# mag_encoder.net
KiCad netlist of a schematic drawn in Altium Designer
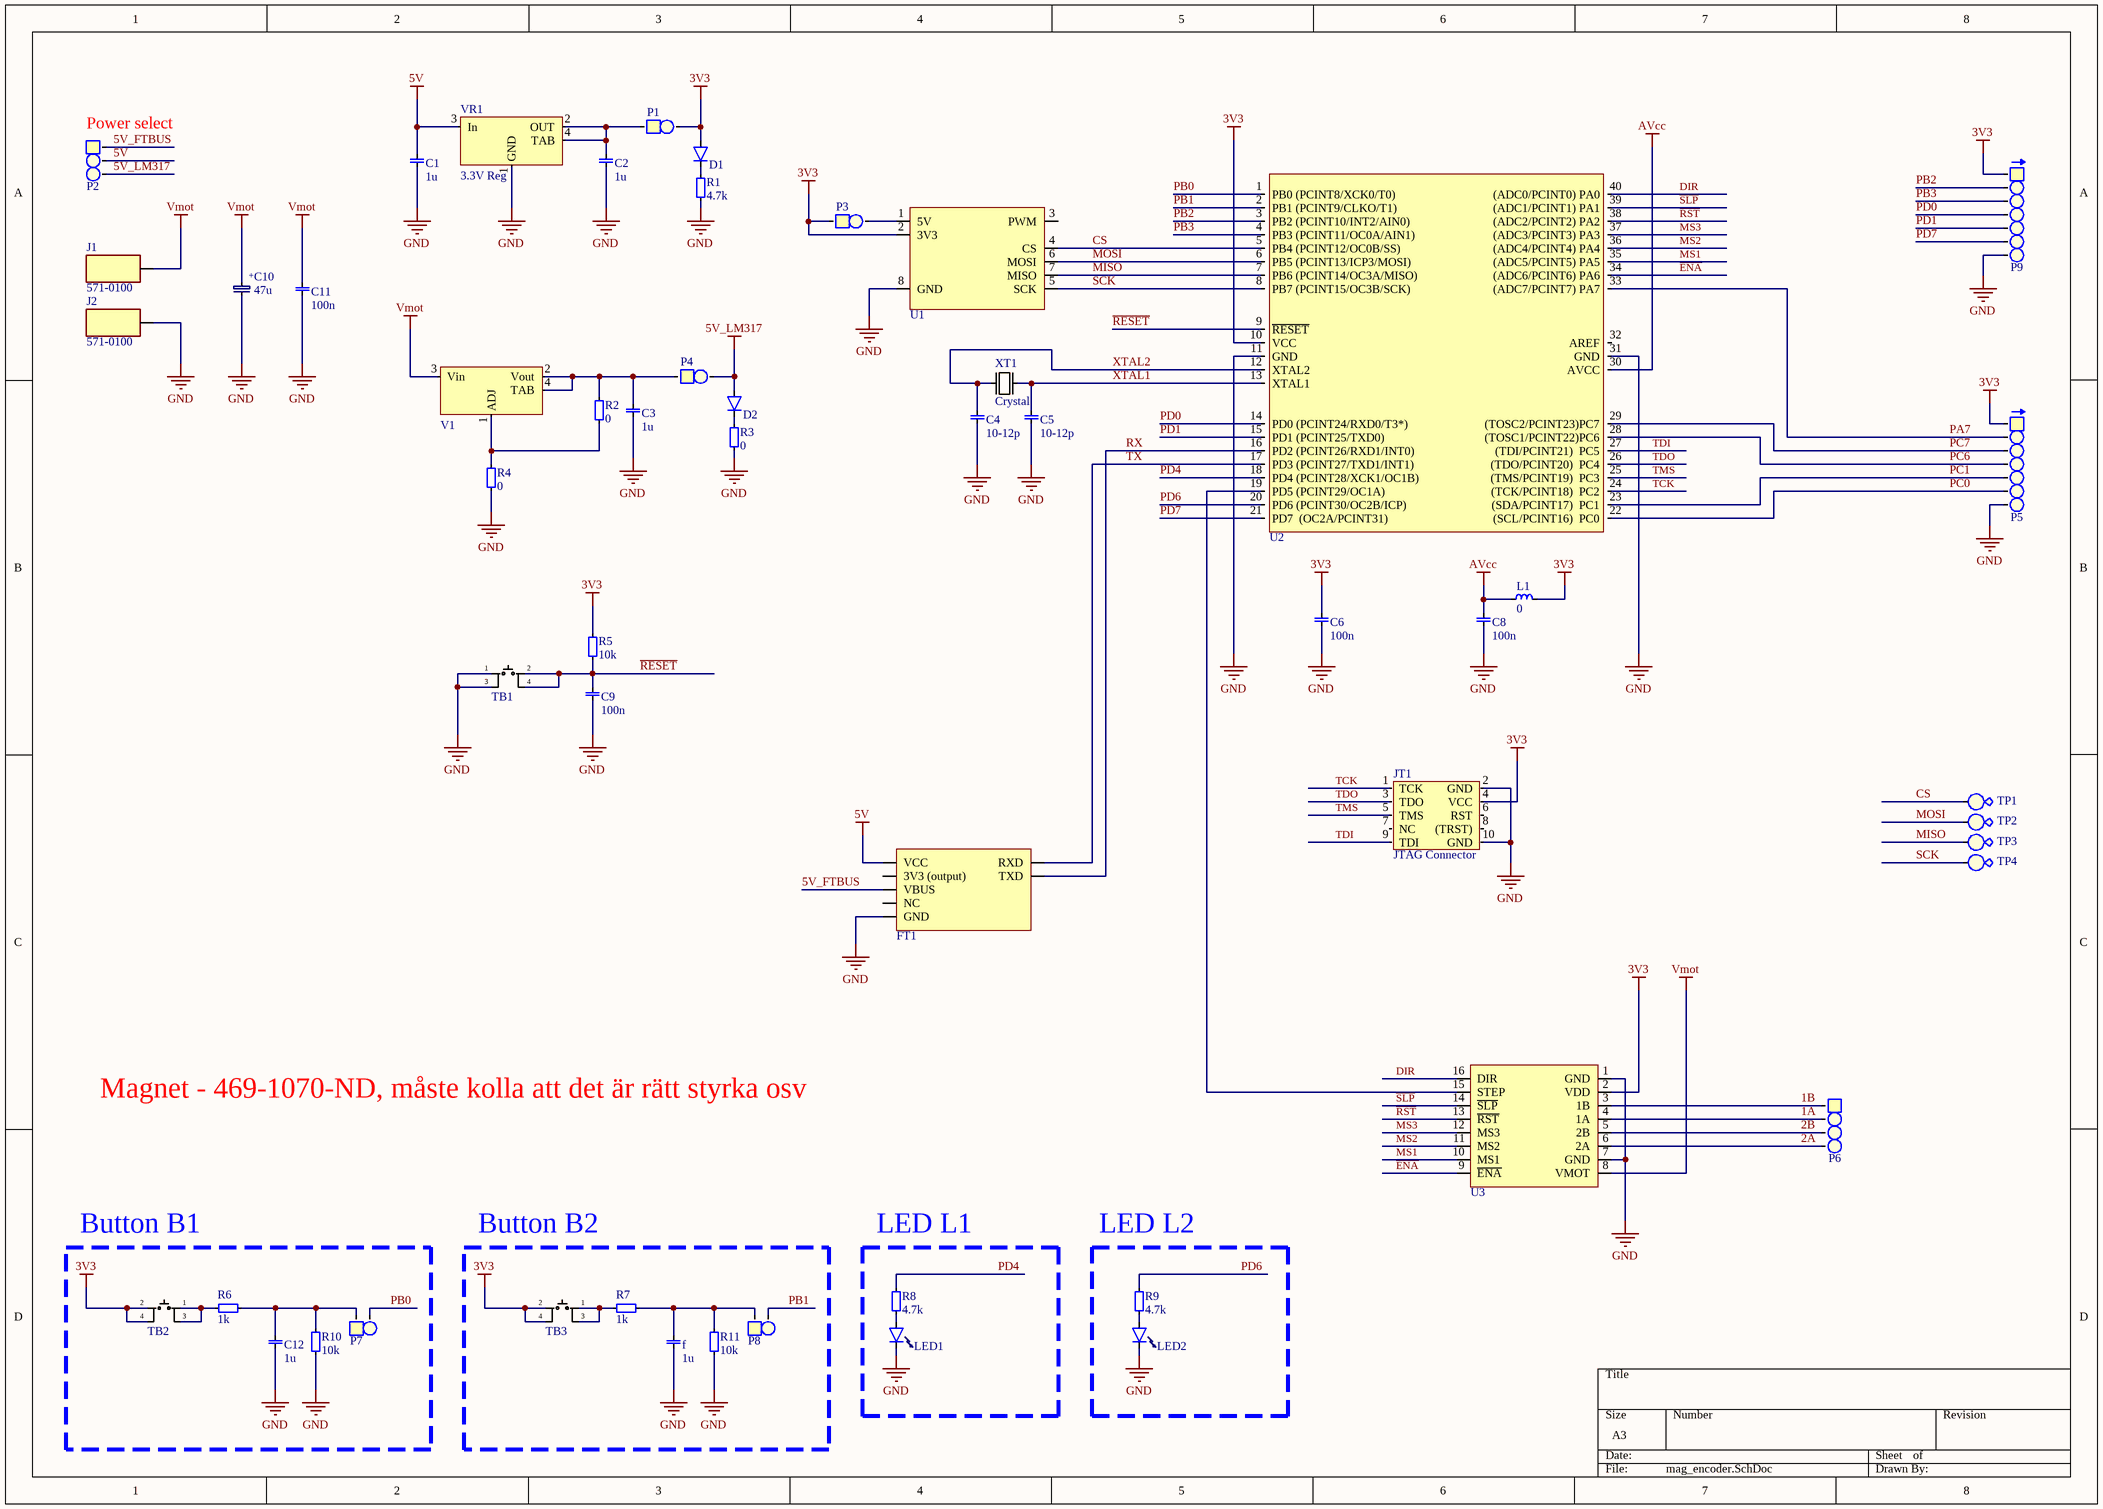
[diagram p0: mag_encoder.SchDoc]

(export (version "E")
  (design (tool "Eeschema 10.0.6"))
  (components
    (comp (ref "C1")
      (value "1u")
      (footprint "0603 cap")
      (fields (field (name "Comment") "0603, capacitor"))
      (libsource (lib "jclib") (part "0603, capacitor"))
    )
    (comp (ref "C2")
      (value "1u")
      (footprint "0603 cap")
      (fields (field (name "Comment") "0603, capacitor"))
      (libsource (lib "jclib") (part "0603, capacitor"))
    )
    (comp (ref "C3")
      (value "1u")
      (footprint "0603 cap")
      (fields (field (name "Comment") "0603, capacitor"))
      (libsource (lib "jclib") (part "0603, capacitor"))
    )
    (comp (ref "C4")
      (value "10-12p")
      (footprint "0603 cap")
      (fields (field (name "Comment") "0603, capacitor"))
      (libsource (lib "jclib") (part "0603, capacitor"))
    )
    (comp (ref "C5")
      (value "10-12p")
      (footprint "0603 cap")
      (fields (field (name "Comment") "0603, capacitor"))
      (libsource (lib "jclib") (part "0603, capacitor"))
    )
    (comp (ref "C6")
      (value "100n")
      (footprint "0603 cap")
      (fields (field (name "Comment") "0603, capacitor"))
      (libsource (lib "jclib") (part "0603, capacitor"))
    )
    (comp (ref "C8")
      (value "100n")
      (footprint "0603 cap")
      (fields (field (name "Comment") "0603, capacitor"))
      (libsource (lib "jclib") (part "0603, capacitor"))
    )
    (comp (ref "C9")
      (value "100n")
      (footprint "0603 cap")
      (fields (field (name "Comment") "0603, capacitor"))
      (libsource (lib "jclib") (part "0603, capacitor"))
    )
    (comp (ref "C10")
      (value "47u")
      (footprint "CASE_B")
      (fields (field (name "Comment") "Cap, case B"))
      (libsource (lib "jclib") (part "Cap, case B"))
    )
    (comp (ref "C11")
      (value "100n")
      (footprint "0805, cap")
      (fields (field (name "Comment") "0805, capacitor"))
      (libsource (lib "jclib") (part "0805, capacitor"))
    )
    (comp (ref "C12")
      (value "1u")
      (footprint "0603 cap")
      (fields (field (name "Comment") "0603, capacitor"))
      (libsource (lib "jclib") (part "0603, capacitor"))
    )
    (comp (ref "D1")
      (value "0805, diode")
      (footprint "0805 diode")
      (libsource (lib "jclib") (part "0805, diode"))
    )
    (comp (ref "D2")
      (value "0805, diode")
      (footprint "0805 diode")
      (libsource (lib "jclib") (part "0805, diode"))
    )
    (comp (ref "f")
      (value "1u")
      (footprint "0603 cap")
      (fields (field (name "Comment") "0603, capacitor"))
      (libsource (lib "jclib") (part "0603, capacitor"))
    )
    (comp (ref "FT1")
      (value "FT232_pcb")
      (footprint "ft2323_pcb")
      (libsource (lib "jclib") (part "FT232_pcb"))
    )
    (comp (ref "J1")
      (value "571-0100")
      (footprint "Banana Conn VCC")
      (description "Banana Connector 571-0100")
      (fields (field (name "MOUSER PART NUMBER") "164-6218"))
      (libsource (lib "jclib") (part "Banana conn"))
    )
    (comp (ref "J2")
      (value "571-0100")
      (footprint "Banana Conn GND")
      (description "Banana Connector 571-0100")
      (fields (field (name "MOUSER PART NUMBER") "164-6218"))
      (libsource (lib "jclib") (part "Banana conn"))
    )
    (comp (ref "JT1")
      (value "JTAG Connector")
      (footprint "Atmel_JTAG")
      (description "Atmel JTAG Connector")
      (libsource (lib "jclib") (part "Atmel JTAG"))
    )
    (comp (ref "L1")
      (value "0")
      (footprint "1812, coil")
      (fields (field (name "Comment") "Coil"))
      (libsource (lib "jclib") (part "Coil"))
    )
    (comp (ref "LED1")
      (value "0805, LED")
      (footprint "0805_led")
      (libsource (lib "eitp15_lab1_lib") (part "0805, LED"))
    )
    (comp (ref "LED2")
      (value "0805, LED")
      (footprint "0805_led")
      (libsource (lib "eitp15_lab1_lib") (part "0805, LED"))
    )
    (comp (ref "P1")
      (value "1x2 Pin Header Straight")
      (footprint "padtwo_L")
      (description "2.54 mm, TH")
      (libsource (lib "jclib") (part "1x2 Pin Header Straight"))
    )
    (comp (ref "P2")
      (value "1x3 Pin Header")
      (footprint "padThree_L")
      (description "2.54 mm")
      (libsource (lib "jclib") (part "1x3 Pin Header"))
    )
    (comp (ref "P3")
      (value "1x2 Pin Header Straight")
      (footprint "padtwo_L")
      (description "2.54 mm, TH")
      (libsource (lib "jclib") (part "1x2 Pin Header Straight"))
    )
    (comp (ref "P4")
      (value "1x2 Pin Header Straight")
      (footprint "padtwo_L")
      (description "2.54 mm, TH")
      (libsource (lib "jclib") (part "1x2 Pin Header Straight"))
    )
    (comp (ref "P5")
      (value "1x7 Pin Header")
      (footprint "1x7 Pin Header")
      (description "2.54 mm")
      (libsource (lib "jclib") (part "1x7 Pin Header"))
    )
    (comp (ref "P6")
      (value "4x1 Pin Header")
      (footprint "padFour_L")
      (description "2.54 mm")
      (libsource (lib "jclib") (part "1x4 Pin Header"))
    )
    (comp (ref "P7")
      (value "1x2 Pin Header")
      (footprint "1x2HEADER")
      (description "2.54 mm, TH")
      (libsource (lib "eitp15_lab1_lib") (part "1x2 Pin Header"))
    )
    (comp (ref "P8")
      (value "1x2 Pin Header")
      (footprint "1x2HEADER")
      (description "2.54 mm, TH")
      (libsource (lib "eitp15_lab1_lib") (part "1x2 Pin Header"))
    )
    (comp (ref "P9")
      (value "1x7 Pin Header")
      (footprint "1x7 Pin Header")
      (description "2.54 mm")
      (libsource (lib "jclib") (part "1x7 Pin Header"))
    )
    (comp (ref "R1")
      (value "4.7k")
      (footprint "0603")
      (fields (field (name "Comment") "0603, resistor"))
      (libsource (lib "jclib") (part "0603, resistor"))
    )
    (comp (ref "R2")
      (value "0")
      (footprint "0603")
      (fields (field (name "Comment") "0603, resistor"))
      (libsource (lib "jclib") (part "0603, resistor"))
    )
    (comp (ref "R3")
      (value "0")
      (footprint "0603")
      (fields (field (name "Comment") "0603, resistor"))
      (libsource (lib "jclib") (part "0603, resistor"))
    )
    (comp (ref "R4")
      (value "0")
      (footprint "0603")
      (fields (field (name "Comment") "0603, resistor"))
      (libsource (lib "jclib") (part "0603, resistor"))
    )
    (comp (ref "R5")
      (value "10k")
      (footprint "0603")
      (fields (field (name "Comment") "0603, resistor"))
      (libsource (lib "jclib") (part "0603, resistor"))
    )
    (comp (ref "R6")
      (value "1k")
      (footprint "0603")
      (fields (field (name "Comment") "0603, resistor"))
      (libsource (lib "jclib") (part "0603, resistor"))
    )
    (comp (ref "R7")
      (value "1k")
      (footprint "0603")
      (fields (field (name "Comment") "0603, resistor"))
      (libsource (lib "jclib") (part "0603, resistor"))
    )
    (comp (ref "R8")
      (value "4.7k")
      (footprint "0603")
      (fields (field (name "Comment") "0603, resistor"))
      (libsource (lib "jclib") (part "0603, resistor"))
    )
    (comp (ref "R9")
      (value "4.7k")
      (footprint "0603")
      (fields (field (name "Comment") "0603, resistor"))
      (libsource (lib "jclib") (part "0603, resistor"))
    )
    (comp (ref "R10")
      (value "10k")
      (footprint "0603")
      (fields (field (name "Comment") "0603, resistor"))
      (libsource (lib "jclib") (part "0603, resistor"))
    )
    (comp (ref "R11")
      (value "10k")
      (footprint "0603")
      (fields (field (name "Comment") "0603, resistor"))
      (libsource (lib "jclib") (part "0603, resistor"))
    )
    (comp (ref "TB1")
      (value "Tactile Button")
      (footprint "Button smd")
      (description "Tactile Switch Small Low")
      (libsource (lib "eitp15_lab1_lib") (part "Button SMD"))
    )
    (comp (ref "TB2")
      (value "Tactile Button")
      (footprint "Button smd")
      (description "Tactile Switch Small Low")
      (libsource (lib "eitp15_lab1_lib") (part "Button SMD"))
    )
    (comp (ref "TB3")
      (value "Tactile Button")
      (footprint "Button smd")
      (description "Tactile Switch Small Low")
      (libsource (lib "eitp15_lab1_lib") (part "Button SMD"))
    )
    (comp (ref "TP1")
      (value "Test Point")
      (footprint "testPoint")
      (libsource (lib "jclib") (part "Test Point"))
    )
    (comp (ref "TP2")
      (value "Test Point")
      (footprint "testPoint")
      (libsource (lib "jclib") (part "Test Point"))
    )
    (comp (ref "TP3")
      (value "Test Point")
      (footprint "testPoint")
      (libsource (lib "jclib") (part "Test Point"))
    )
    (comp (ref "TP4")
      (value "Test Point")
      (footprint "testPoint")
      (libsource (lib "jclib") (part "Test Point"))
    )
    (comp (ref "U1")
      (value "as5048_module")
      (footprint "AS5048_MODULE")
      (description "AS5048 Rotary encoder")
      (libsource (lib "jclib") (part "as5048_module"))
    )
    (comp (ref "U2")
      (value "ATmega1284")
      (footprint "DIP40")
      (description "8-bit Atmel Microcontroller with 128K Bytes  In-System Programmable Flash")
      (libsource (lib "jclib") (part "ATmega1284"))
    )
    (comp (ref "U3")
      (value "A4988_stepstick")
      (footprint "A4988_stepstick")
      (libsource (lib "jclib") (part "A4988_stepstick"))
    )
    (comp (ref "V1")
      (value "LM317")
      (footprint "SOT223")
      (description "Adjustable Voltage Regulator")
      (libsource (lib "jclib") (part "LM317 SOT223"))
    )
    (comp (ref "VR1")
      (value "3.3V Reg")
      (footprint "SOT223")
      (description "TLV1117LV 1-A, Positive Fixed-Voltage, Low-Dropout Regulator")
      (libsource (lib "jclib") (part "TLV1117LV"))
    )
    (comp (ref "XT1")
      (value "Crystal")
      (footprint "XTAL_SMD_LP")
      (description "16 MHz, SMD, 5mm x 3,2mm, 30 ppm")
      (fields (field (name "Comment") "XTAL TXC 7A"))
      (libsource (lib "eitp15_lab1_lib") (part "XTAL TXC 7A"))
    )
  )
  (nets
    (net (code "1") (name "/1A") (class "Default")
      (node (ref "P6") (pin "2") (pinfunction "2_2") (pintype "passive"))
      (node (ref "U3") (pin "4") (pinfunction "1A_4") (pintype "passive"))
    )
    (net (code "2") (name "/1B") (class "Default")
      (node (ref "P6") (pin "1") (pinfunction "1_1") (pintype "passive"))
      (node (ref "U3") (pin "3") (pinfunction "1B_3") (pintype "passive"))
    )
    (net (code "3") (name "/2A") (class "Default")
      (node (ref "P6") (pin "4") (pinfunction "4_4") (pintype "passive"))
      (node (ref "U3") (pin "6") (pinfunction "2A_6") (pintype "passive"))
    )
    (net (code "4") (name "/2B") (class "Default")
      (node (ref "P6") (pin "3") (pinfunction "3_3") (pintype "passive"))
      (node (ref "U3") (pin "5") (pinfunction "2B_5") (pintype "passive"))
    )
    (net (code "5") (name "/5V_FTBUS") (class "Default")
      (node (ref "FT1") (pin "3") (pinfunction "VBUS_3") (pintype "passive"))
      (node (ref "P2") (pin "1") (pinfunction "1_1") (pintype "passive"))
    )
    (net (code "6") (name "/CS") (class "Default")
      (node (ref "TP1") (pin "0") (pinfunction "0_0") (pintype "passive"))
      (node (ref "U1") (pin "4") (pinfunction "CS_4") (pintype "passive"))
      (node (ref "U2") (pin "5") (pinfunction "PB4_(PCINT12/OC0B/SS)_5") (pintype "passive"))
    )
    (net (code "7") (name "/DIR") (class "Default")
      (node (ref "U2") (pin "40") (pinfunction "(ADC0/PCINT0)_PA0_40") (pintype "passive"))
      (node (ref "U3") (pin "16") (pinfunction "DIR_16") (pintype "passive"))
    )
    (net (code "8") (name "/MISO") (class "Default")
      (node (ref "TP3") (pin "0") (pinfunction "0_0") (pintype "passive"))
      (node (ref "U1") (pin "7") (pinfunction "MISO_7") (pintype "passive"))
      (node (ref "U2") (pin "7") (pinfunction "PB6_(PCINT14/OC3A/MISO)_7") (pintype "passive"))
    )
    (net (code "9") (name "/MOSI") (class "Default")
      (node (ref "TP2") (pin "0") (pinfunction "0_0") (pintype "passive"))
      (node (ref "U1") (pin "6") (pinfunction "MOSI_6") (pintype "passive"))
      (node (ref "U2") (pin "6") (pinfunction "PB5_(PCINT13/ICP3/MOSI)_6") (pintype "passive"))
    )
    (net (code "10") (name "/MS1") (class "Default")
      (node (ref "U2") (pin "35") (pinfunction "(ADC5/PCINT5)_PA5_35") (pintype "passive"))
      (node (ref "U3") (pin "10") (pinfunction "MS1_10") (pintype "passive"))
    )
    (net (code "11") (name "/MS2") (class "Default")
      (node (ref "U2") (pin "36") (pinfunction "(ADC4/PCINT4)_PA4_36") (pintype "passive"))
      (node (ref "U3") (pin "11") (pinfunction "MS2_11") (pintype "passive"))
    )
    (net (code "12") (name "/MS3") (class "Default")
      (node (ref "U2") (pin "37") (pinfunction "(ADC3/PCINT3)_PA3_37") (pintype "passive"))
      (node (ref "U3") (pin "12") (pinfunction "MS3_12") (pintype "passive"))
    )
    (net (code "13") (name "/PA7") (class "Default")
      (node (ref "P5") (pin "2") (pinfunction "2_2") (pintype "passive"))
      (node (ref "U2") (pin "33") (pinfunction "(ADC7/PCINT7)_PA7_33") (pintype "passive"))
    )
    (net (code "14") (name "/PB0") (class "Default")
      (node (ref "P7") (pin "2") (pinfunction "2_2") (pintype "passive"))
      (node (ref "U2") (pin "1") (pinfunction "PB0_(PCINT8/XCK0/T0)_1") (pintype "passive"))
    )
    (net (code "15") (name "/PB1") (class "Default")
      (node (ref "P8") (pin "2") (pinfunction "2_2") (pintype "passive"))
      (node (ref "U2") (pin "2") (pinfunction "PB1_(PCINT9/CLKO/T1)_2") (pintype "passive"))
    )
    (net (code "16") (name "/PB2") (class "Default")
      (node (ref "P9") (pin "2") (pinfunction "2_2") (pintype "passive"))
      (node (ref "U2") (pin "3") (pinfunction "PB2_(PCINT10/INT2/AIN0)_3") (pintype "passive"))
    )
    (net (code "17") (name "/PB3") (class "Default")
      (node (ref "P9") (pin "3") (pinfunction "3_3") (pintype "passive"))
      (node (ref "U2") (pin "4") (pinfunction "PB3_(PCINT11/OC0A/AIN1)_4") (pintype "passive"))
    )
    (net (code "18") (name "/PC0") (class "Default")
      (node (ref "P5") (pin "6") (pinfunction "6_6") (pintype "passive"))
      (node (ref "U2") (pin "22") (pinfunction "(SCL/PCINT16)__PC0_22") (pintype "passive"))
    )
    (net (code "19") (name "/PC1") (class "Default")
      (node (ref "P5") (pin "5") (pinfunction "5_5") (pintype "passive"))
      (node (ref "U2") (pin "23") (pinfunction "(SDA/PCINT17)__PC1_23") (pintype "passive"))
    )
    (net (code "20") (name "/PC6") (class "Default")
      (node (ref "P5") (pin "4") (pinfunction "4_4") (pintype "passive"))
      (node (ref "U2") (pin "28") (pinfunction "(TOSC1/PCINT22)PC6_28") (pintype "passive"))
    )
    (net (code "21") (name "/PC7") (class "Default")
      (node (ref "P5") (pin "3") (pinfunction "3_3") (pintype "passive"))
      (node (ref "U2") (pin "29") (pinfunction "(TOSC2/PCINT23)PC7_29") (pintype "passive"))
    )
    (net (code "22") (name "/PD0") (class "Default")
      (node (ref "P9") (pin "4") (pinfunction "4_4") (pintype "passive"))
      (node (ref "U2") (pin "14") (pinfunction "PD0_(PCINT24/RXD0/T3*)_14") (pintype "passive"))
    )
    (net (code "23") (name "/PD1") (class "Default")
      (node (ref "P9") (pin "5") (pinfunction "5_5") (pintype "passive"))
      (node (ref "U2") (pin "15") (pinfunction "PD1_(PCINT25/TXD0)_15") (pintype "passive"))
    )
    (net (code "24") (name "/PD4") (class "Default")
      (node (ref "R8") (pin "0") (pinfunction "0_0") (pintype "passive"))
      (node (ref "U2") (pin "18") (pinfunction "PD4_(PCINT28/XCK1/OC1B)_18") (pintype "passive"))
    )
    (net (code "25") (name "/PD6") (class "Default")
      (node (ref "R9") (pin "0") (pinfunction "0_0") (pintype "passive"))
      (node (ref "U2") (pin "20") (pinfunction "PD6_(PCINT30/OC2B/ICP)_20") (pintype "passive"))
    )
    (net (code "26") (name "/PD7") (class "Default")
      (node (ref "P9") (pin "6") (pinfunction "6_6") (pintype "passive"))
      (node (ref "U2") (pin "21") (pinfunction "PD7__(OC2A/PCINT31)_21") (pintype "passive"))
    )
    (net (code "27") (name "/RX") (class "Default")
      (node (ref "FT1") (pin "4") (pinfunction "TXD_4") (pintype "passive"))
      (node (ref "U2") (pin "16") (pinfunction "PD2_(PCINT26/RXD1/INT0)_16") (pintype "passive"))
    )
    (net (code "28") (name "/SCK") (class "Default")
      (node (ref "TP4") (pin "0") (pinfunction "0_0") (pintype "passive"))
      (node (ref "U1") (pin "5") (pinfunction "SCK_5") (pintype "passive"))
      (node (ref "U2") (pin "8") (pinfunction "PB7_(PCINT15/OC3B/SCK)_8") (pintype "passive"))
    )
    (net (code "29") (name "/TCK") (class "Default")
      (node (ref "JT1") (pin "1") (pinfunction "TCK_1") (pintype "passive"))
      (node (ref "U2") (pin "24") (pinfunction "(TCK/PCINT18)__PC2_24") (pintype "passive"))
    )
    (net (code "30") (name "/TDI") (class "Default")
      (node (ref "JT1") (pin "9") (pinfunction "TDI_9") (pintype "passive"))
      (node (ref "U2") (pin "27") (pinfunction "(TDI/PCINT21)__PC5_27") (pintype "passive"))
    )
    (net (code "31") (name "/TDO") (class "Default")
      (node (ref "JT1") (pin "3") (pinfunction "TDO_3") (pintype "passive"))
      (node (ref "U2") (pin "26") (pinfunction "(TDO/PCINT20)__PC4_26") (pintype "passive"))
    )
    (net (code "32") (name "/TMS") (class "Default")
      (node (ref "JT1") (pin "5") (pinfunction "TMS_5") (pintype "passive"))
      (node (ref "U2") (pin "25") (pinfunction "(TMS/PCINT19)__PC3_25") (pintype "passive"))
    )
    (net (code "33") (name "/TX") (class "Default")
      (node (ref "FT1") (pin "5") (pinfunction "RXD_5") (pintype "passive"))
      (node (ref "U2") (pin "17") (pinfunction "PD3_(PCINT27/TXD1/INT1)_17") (pintype "passive"))
    )
    (net (code "34") (name "/XTAL1") (class "Default")
      (node (ref "C5") (pin "1") (pinfunction "1_1") (pintype "passive"))
      (node (ref "U2") (pin "13") (pinfunction "XTAL1_13") (pintype "passive"))
      (node (ref "XT1") (pin "1") (pinfunction "1_1") (pintype "passive"))
    )
    (net (code "35") (name "/XTAL2") (class "Default")
      (node (ref "C4") (pin "1") (pinfunction "1_1") (pintype "passive"))
      (node (ref "U2") (pin "12") (pinfunction "XTAL2_12") (pintype "passive"))
      (node (ref "XT1") (pin "2") (pinfunction "2_2") (pintype "passive"))
    )
    (net (code "36") (name "/~{ENA}") (class "Default")
      (node (ref "U2") (pin "34") (pinfunction "(ADC6/PCINT6)_PA6_34") (pintype "passive"))
      (node (ref "U3") (pin "9") (pinfunction "~{ENA}_9") (pintype "passive"))
    )
    (net (code "37") (name "/~{RESET}") (class "Default")
      (node (ref "C9") (pin "1") (pinfunction "1_1") (pintype "passive"))
      (node (ref "R5") (pin "1") (pinfunction "1_1") (pintype "passive"))
      (node (ref "TB1") (pin "2") (pinfunction "2_2") (pintype "passive"))
      (node (ref "TB1") (pin "4") (pinfunction "4_4") (pintype "passive"))
      (node (ref "U2") (pin "9") (pinfunction "~{RESET}_9") (pintype "passive"))
    )
    (net (code "38") (name "/~{RST}") (class "Default")
      (node (ref "U2") (pin "38") (pinfunction "(ADC2/PCINT2)_PA2_38") (pintype "passive"))
      (node (ref "U3") (pin "13") (pinfunction "~{RST}_13") (pintype "passive"))
    )
    (net (code "39") (name "/~{SLP}") (class "Default")
      (node (ref "U2") (pin "39") (pinfunction "(ADC1/PCINT1)_PA1_39") (pintype "passive"))
      (node (ref "U3") (pin "14") (pinfunction "~{SLP}_14") (pintype "passive"))
    )
    (net (code "40") (name "3V3") (class "Default")
      (node (ref "C6") (pin "1") (pinfunction "1_1") (pintype "passive"))
      (node (ref "D1") (pin "1") (pinfunction "1_1") (pintype "passive"))
      (node (ref "JT1") (pin "4") (pinfunction "VCC_4") (pintype "passive"))
      (node (ref "L1") (pin "1") (pinfunction "1_1") (pintype "passive"))
      (node (ref "P1") (pin "2") (pinfunction "2_2") (pintype "passive"))
      (node (ref "P3") (pin "1") (pinfunction "1_1") (pintype "passive"))
      (node (ref "P5") (pin "1") (pinfunction "1_1") (pintype "passive"))
      (node (ref "P9") (pin "1") (pinfunction "1_1") (pintype "passive"))
      (node (ref "R5") (pin "0") (pinfunction "0_0") (pintype "passive"))
      (node (ref "TB2") (pin "2") (pinfunction "2_2") (pintype "passive"))
      (node (ref "TB2") (pin "4") (pinfunction "4_4") (pintype "passive"))
      (node (ref "TB3") (pin "2") (pinfunction "2_2") (pintype "passive"))
      (node (ref "TB3") (pin "4") (pinfunction "4_4") (pintype "passive"))
      (node (ref "U1") (pin "2") (pinfunction "3V3_2") (pintype "passive"))
      (node (ref "U2") (pin "10") (pinfunction "VCC_10") (pintype "passive"))
      (node (ref "U3") (pin "2") (pinfunction "VDD_2") (pintype "passive"))
    )
    (net (code "41") (name "5V") (class "Default")
      (node (ref "C1") (pin "1") (pinfunction "1_1") (pintype "passive"))
      (node (ref "FT1") (pin "1") (pinfunction "VCC_1") (pintype "passive"))
      (node (ref "P2") (pin "2") (pinfunction "2_2") (pintype "passive"))
      (node (ref "VR1") (pin "3") (pinfunction "In_3") (pintype "passive"))
    )
    (net (code "42") (name "5V_LM317") (class "Default")
      (node (ref "D2") (pin "1") (pinfunction "1_1") (pintype "passive"))
      (node (ref "P2") (pin "3") (pinfunction "3_3") (pintype "passive"))
      (node (ref "P4") (pin "2") (pinfunction "2_2") (pintype "passive"))
    )
    (net (code "43") (name "AVcc") (class "Default")
      (node (ref "C8") (pin "1") (pinfunction "1_1") (pintype "passive"))
      (node (ref "L1") (pin "2") (pinfunction "2_2") (pintype "passive"))
      (node (ref "U2") (pin "30") (pinfunction "AVCC_30") (pintype "passive"))
    )
    (net (code "44") (name "GND") (class "Default")
      (node (ref "C1") (pin "0") (pinfunction "0_0") (pintype "passive"))
      (node (ref "C10") (pin "1") (pinfunction "1_1") (pintype "passive"))
      (node (ref "C11") (pin "0") (pinfunction "0_0") (pintype "passive"))
      (node (ref "C12") (pin "0") (pinfunction "0_0") (pintype "passive"))
      (node (ref "C2") (pin "0") (pinfunction "0_0") (pintype "passive"))
      (node (ref "C3") (pin "0") (pinfunction "0_0") (pintype "passive"))
      (node (ref "C4") (pin "0") (pinfunction "0_0") (pintype "passive"))
      (node (ref "C5") (pin "0") (pinfunction "0_0") (pintype "passive"))
      (node (ref "C6") (pin "0") (pinfunction "0_0") (pintype "passive"))
      (node (ref "C8") (pin "0") (pinfunction "0_0") (pintype "passive"))
      (node (ref "C9") (pin "0") (pinfunction "0_0") (pintype "passive"))
      (node (ref "FT1") (pin "7") (pinfunction "GND_7") (pintype "passive"))
      (node (ref "J2") (pin "1") (pinfunction "1_1") (pintype "passive"))
      (node (ref "JT1") (pin "10") (pinfunction "GND_10") (pintype "passive"))
      (node (ref "JT1") (pin "2") (pinfunction "GND_2") (pintype "passive"))
      (node (ref "LED1") (pin "0") (pinfunction "Cathode_0") (pintype "passive"))
      (node (ref "LED2") (pin "0") (pinfunction "Cathode_0") (pintype "passive"))
      (node (ref "P5") (pin "7") (pinfunction "7_7") (pintype "passive"))
      (node (ref "P9") (pin "7") (pinfunction "7_7") (pintype "passive"))
      (node (ref "R1") (pin "1") (pinfunction "1_1") (pintype "passive"))
      (node (ref "R10") (pin "1") (pinfunction "1_1") (pintype "passive"))
      (node (ref "R11") (pin "1") (pinfunction "1_1") (pintype "passive"))
      (node (ref "R3") (pin "1") (pinfunction "1_1") (pintype "passive"))
      (node (ref "R4") (pin "1") (pinfunction "1_1") (pintype "passive"))
      (node (ref "TB1") (pin "1") (pinfunction "1_1") (pintype "passive"))
      (node (ref "TB1") (pin "3") (pinfunction "3_3") (pintype "passive"))
      (node (ref "U1") (pin "8") (pinfunction "GND_8") (pintype "passive"))
      (node (ref "U2") (pin "11") (pinfunction "GND_11") (pintype "passive"))
      (node (ref "U2") (pin "31") (pinfunction "GND_31") (pintype "passive"))
      (node (ref "U3") (pin "1") (pinfunction "GND_1") (pintype "passive"))
      (node (ref "U3") (pin "7") (pinfunction "GND_7") (pintype "passive"))
      (node (ref "VR1") (pin "1") (pinfunction "GND_1") (pintype "passive"))
      (node (ref "f") (pin "0") (pinfunction "0_0") (pintype "passive"))
    )
    (net (code "45") (name "Net-(C12-Pad1)") (class "Default")
      (node (ref "C12") (pin "1") (pinfunction "1_1") (pintype "passive"))
      (node (ref "P7") (pin "1") (pinfunction "1_1") (pintype "passive"))
      (node (ref "R10") (pin "0") (pinfunction "0_0") (pintype "passive"))
      (node (ref "R6") (pin "0") (pinfunction "0_0") (pintype "passive"))
    )
    (net (code "46") (name "Net-(D1-Cathode)") (class "Default")
      (node (ref "D1") (pin "0") (pinfunction "Cathode_0") (pintype "passive"))
      (node (ref "R1") (pin "0") (pinfunction "0_0") (pintype "passive"))
    )
    (net (code "47") (name "Net-(D2-Cathode)") (class "Default")
      (node (ref "D2") (pin "0") (pinfunction "Cathode_0") (pintype "passive"))
      (node (ref "R3") (pin "0") (pinfunction "0_0") (pintype "passive"))
    )
    (net (code "48") (name "Net-(LED1-Pad1)") (class "Default")
      (node (ref "LED1") (pin "1") (pinfunction "1_1") (pintype "passive"))
      (node (ref "R8") (pin "1") (pinfunction "1_1") (pintype "passive"))
    )
    (net (code "49") (name "Net-(LED2-Pad1)") (class "Default")
      (node (ref "LED2") (pin "1") (pinfunction "1_1") (pintype "passive"))
      (node (ref "R9") (pin "1") (pinfunction "1_1") (pintype "passive"))
    )
    (net (code "50") (name "Net-(P8-Pad1)") (class "Default")
      (node (ref "P8") (pin "1") (pinfunction "1_1") (pintype "passive"))
      (node (ref "R11") (pin "0") (pinfunction "0_0") (pintype "passive"))
      (node (ref "R7") (pin "0") (pinfunction "0_0") (pintype "passive"))
      (node (ref "f") (pin "1") (pinfunction "1_1") (pintype "passive"))
    )
    (net (code "51") (name "Net-(R6-Pad1)") (class "Default")
      (node (ref "R6") (pin "1") (pinfunction "1_1") (pintype "passive"))
      (node (ref "TB2") (pin "1") (pinfunction "1_1") (pintype "passive"))
      (node (ref "TB2") (pin "3") (pinfunction "3_3") (pintype "passive"))
    )
    (net (code "52") (name "Net-(R7-Pad1)") (class "Default")
      (node (ref "R7") (pin "1") (pinfunction "1_1") (pintype "passive"))
      (node (ref "TB3") (pin "1") (pinfunction "1_1") (pintype "passive"))
      (node (ref "TB3") (pin "3") (pinfunction "3_3") (pintype "passive"))
    )
    (net (code "53") (name "Net-(U1-5V)") (class "Default")
      (node (ref "P3") (pin "2") (pinfunction "2_2") (pintype "passive"))
      (node (ref "U1") (pin "1") (pinfunction "5V_1") (pintype "passive"))
    )
    (net (code "54") (name "Net-(U2-PD5_(PCINT29{slash}OC1A))") (class "Default")
      (node (ref "U2") (pin "19") (pinfunction "PD5_(PCINT29/OC1A)_19") (pintype "passive"))
      (node (ref "U3") (pin "15") (pinfunction "STEP_15") (pintype "passive"))
    )
    (net (code "55") (name "Net-(V1-ADJ)") (class "Default")
      (node (ref "R2") (pin "1") (pinfunction "1_1") (pintype "passive"))
      (node (ref "R4") (pin "0") (pinfunction "0_0") (pintype "passive"))
      (node (ref "V1") (pin "1") (pinfunction "ADJ_1") (pintype "passive"))
    )
    (net (code "56") (name "Net-(V1-TAB)") (class "Default")
      (node (ref "C3") (pin "1") (pinfunction "1_1") (pintype "passive"))
      (node (ref "P4") (pin "1") (pinfunction "1_1") (pintype "passive"))
      (node (ref "R2") (pin "0") (pinfunction "0_0") (pintype "passive"))
      (node (ref "V1") (pin "2") (pinfunction "Vout_2") (pintype "passive"))
      (node (ref "V1") (pin "4") (pinfunction "TAB_4") (pintype "passive"))
    )
    (net (code "57") (name "Net-(VR1-OUT)") (class "Default")
      (node (ref "C2") (pin "1") (pinfunction "1_1") (pintype "passive"))
      (node (ref "P1") (pin "1") (pinfunction "1_1") (pintype "passive"))
      (node (ref "VR1") (pin "2") (pinfunction "OUT_2") (pintype "passive"))
      (node (ref "VR1") (pin "4") (pinfunction "TAB_4") (pintype "passive"))
    )
    (net (code "58") (name "Vmot") (class "Default")
      (node (ref "C10") (pin "2") (pinfunction "2_2") (pintype "passive"))
      (node (ref "C11") (pin "1") (pinfunction "1_1") (pintype "passive"))
      (node (ref "J1") (pin "1") (pinfunction "1_1") (pintype "passive"))
      (node (ref "U3") (pin "8") (pinfunction "VMOT_8") (pintype "passive"))
      (node (ref "V1") (pin "3") (pinfunction "Vin_3") (pintype "passive"))
    )
    (net (code "59") (name "unconnected-(FT1-3V3_(output)-Pad2)") (class "Default")
      (node (ref "FT1") (pin "2") (pinfunction "3V3_(output)_2") (pintype "passive"))
    )
    (net (code "60") (name "unconnected-(FT1-NC-Pad6)") (class "Default")
      (node (ref "FT1") (pin "6") (pinfunction "NC_6") (pintype "passive"))
    )
    (net (code "61") (name "unconnected-(JT1-(TRST)-Pad8)") (class "Default")
      (node (ref "JT1") (pin "8") (pinfunction "(TRST)_8") (pintype "passive"))
    )
    (net (code "62") (name "unconnected-(JT1-NC-Pad7)") (class "Default")
      (node (ref "JT1") (pin "7") (pinfunction "NC_7") (pintype "passive"))
    )
    (net (code "63") (name "unconnected-(JT1-RST-Pad6)") (class "Default")
      (node (ref "JT1") (pin "6") (pinfunction "RST_6") (pintype "passive"))
    )
    (net (code "64") (name "unconnected-(U1-PWM-Pad3)") (class "Default")
      (node (ref "U1") (pin "3") (pinfunction "PWM_3") (pintype "passive"))
    )
    (net (code "65") (name "unconnected-(U2-AREF-Pad32)") (class "Default")
      (node (ref "U2") (pin "32") (pinfunction "AREF_32") (pintype "passive"))
    )
  )
)
